# Group_02.net
KiCad netlist of a schematic drawn in EAGLE
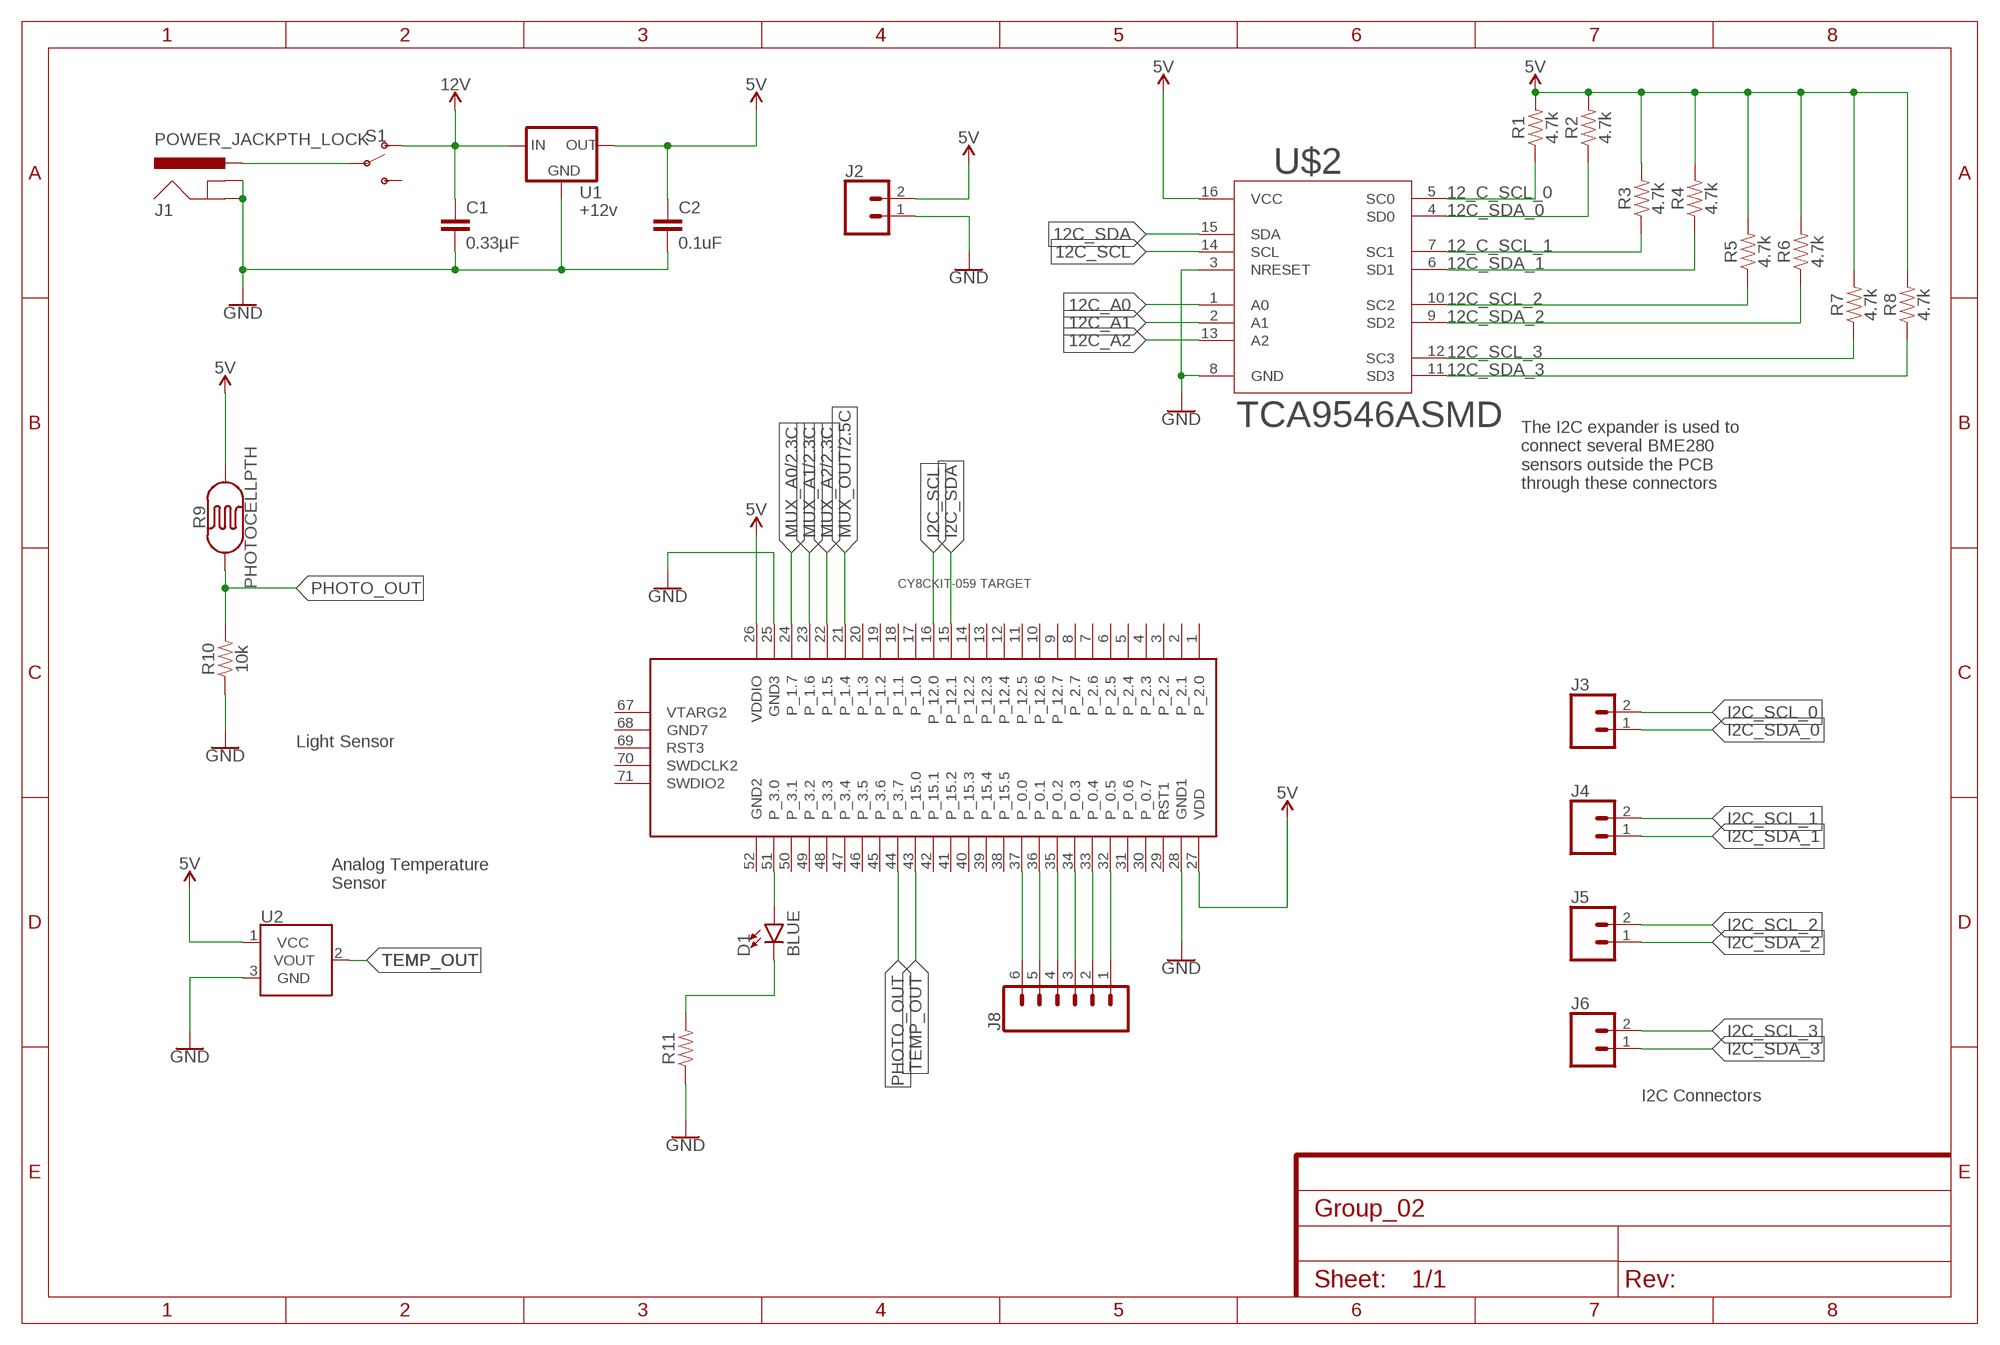
[diagram p0: schematic, sheet 1, part 1 of 2]
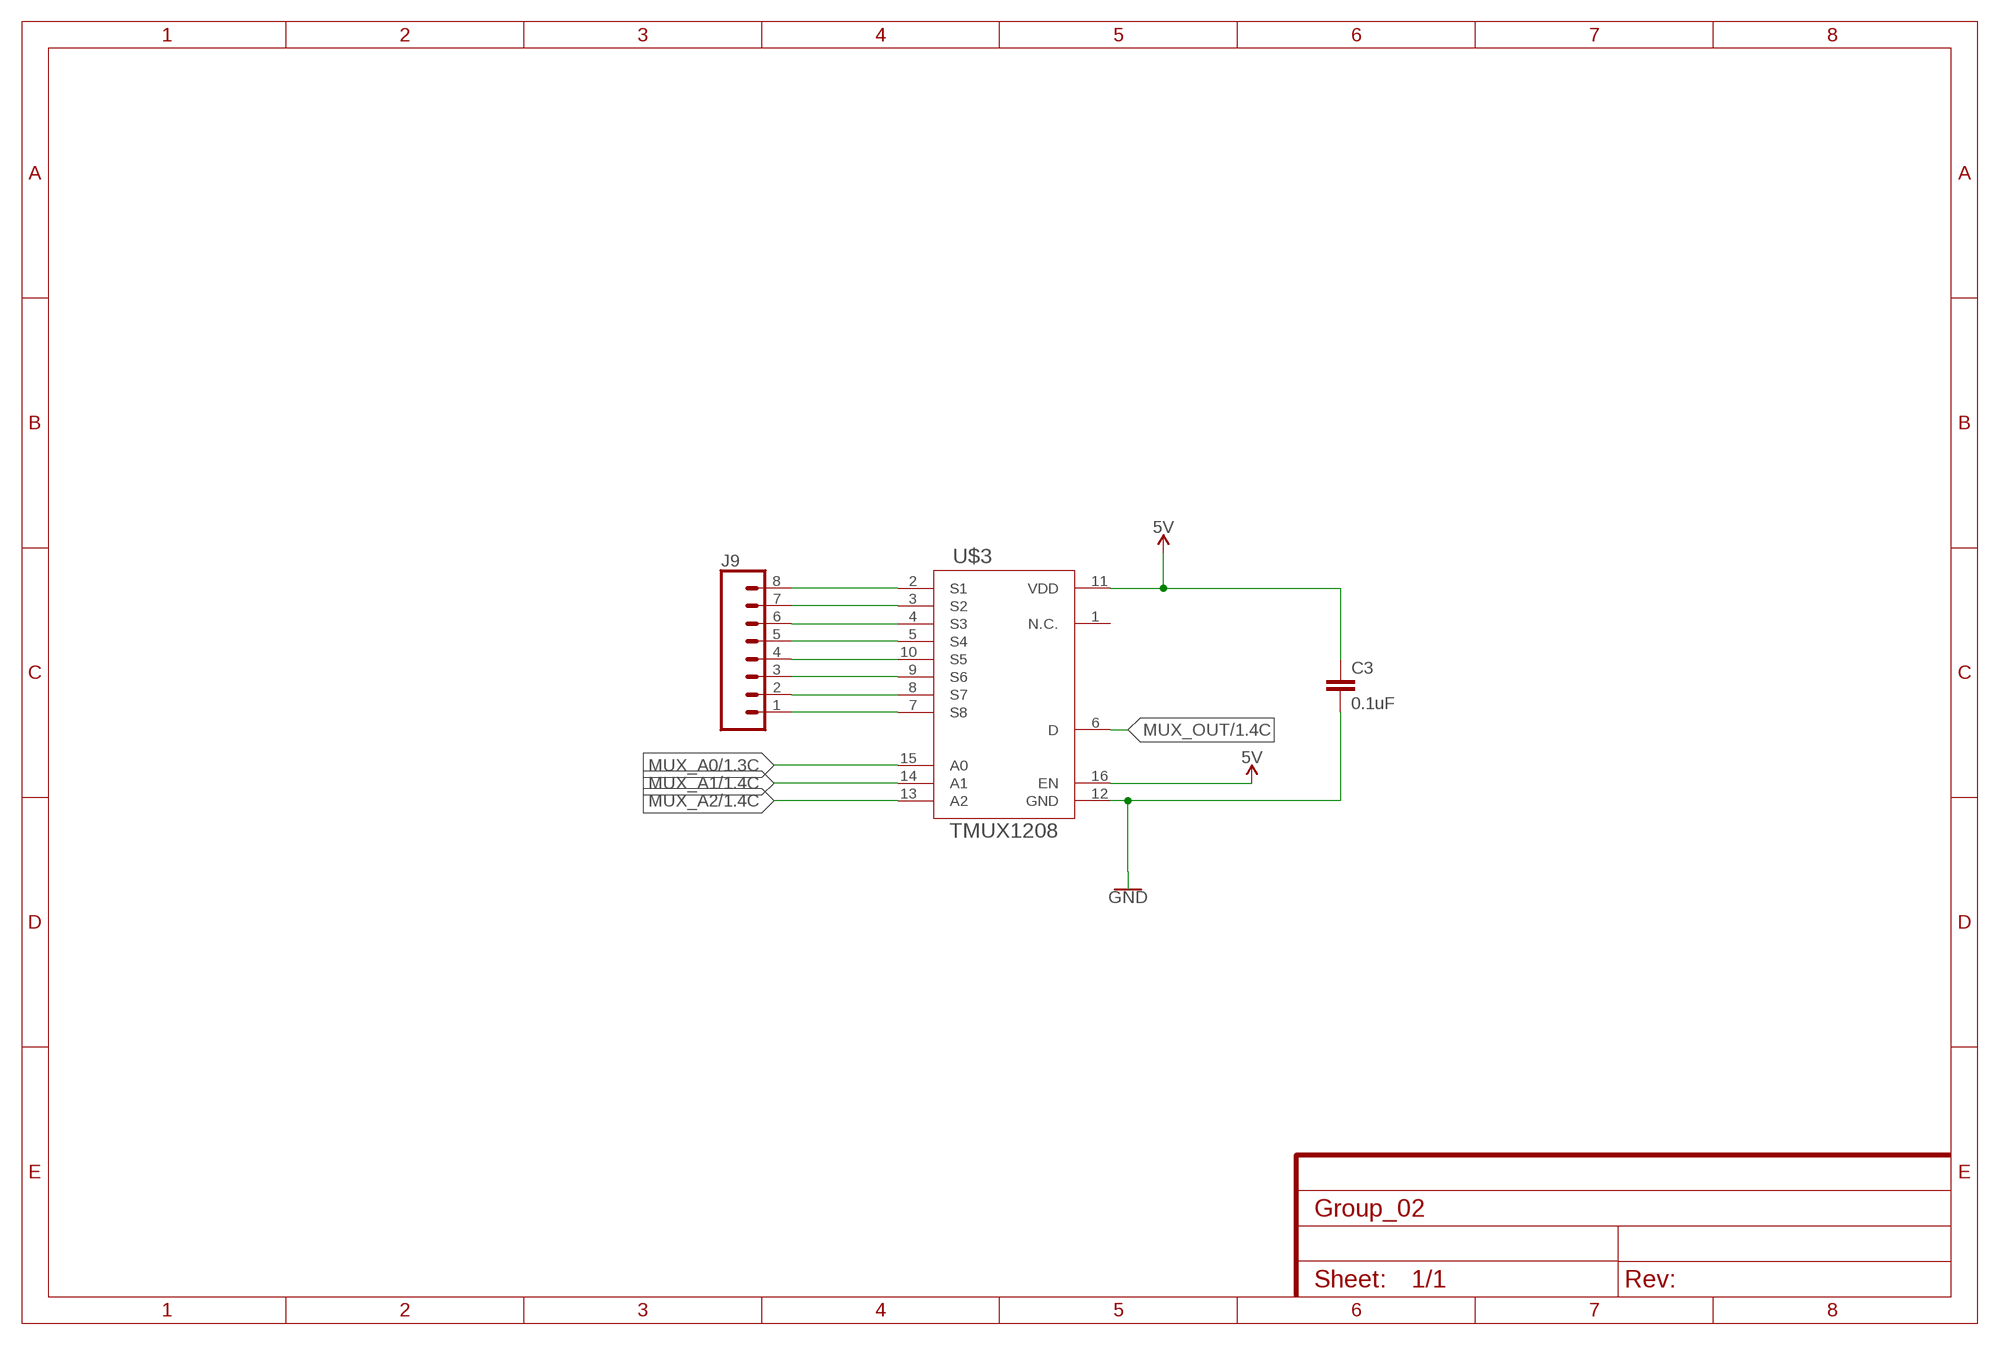
[diagram p1: schematic, sheet 1, part 2 of 2]

(export (version "E")
  (design (tool "Eeschema 10.0.6"))
  (components
    (comp (ref "C1")
      (value "0.33µF")
      (footprint "eagle-import:0805")
      (libsource (lib "eagle-import") (part "0.33UF/330NF-0805-50V-10%"))
    )
    (comp (ref "C2")
      (value "0.1uF")
      (footprint "eagle-import:CAP-PTH-SMALL-KIT")
      (libsource (lib "eagle-import") (part "0.1UF-KIT-EZ-50V-20%"))
    )
    (comp (ref "C3")
      (value "0.1uF")
      (footprint "eagle-import:CAP-PTH-SMALL-KIT")
      (libsource (lib "eagle-import") (part "0.1UF-KIT-EZ-50V-20%"))
    )
    (comp (ref "D1")
      (value "BLUE")
      (footprint "eagle-import:LED-1206")
      (libsource (lib "eagle-import") (part "LED-BLUE1206"))
    )
    (comp (ref "J1")
      (value "POWER_JACKPTH_LOCK")
      (footprint "eagle-import:POWER_JACK_PTH_LOCK")
      (libsource (lib "eagle-import") (part "POWER_JACKPTH_LOCK"))
    )
    (comp (ref "J2")
      (value "CONN_02")
      (footprint "eagle-import:1X02")
      (libsource (lib "eagle-import") (part "CONN_02"))
    )
    (comp (ref "J3")
      (value "CONN_02")
      (footprint "eagle-import:1X02")
      (libsource (lib "eagle-import") (part "CONN_02"))
    )
    (comp (ref "J4")
      (value "CONN_02")
      (footprint "eagle-import:1X02")
      (libsource (lib "eagle-import") (part "CONN_02"))
    )
    (comp (ref "J5")
      (value "CONN_02")
      (footprint "eagle-import:1X02")
      (libsource (lib "eagle-import") (part "CONN_02"))
    )
    (comp (ref "J6")
      (value "CONN_02")
      (footprint "eagle-import:1X02")
      (libsource (lib "eagle-import") (part "CONN_02"))
    )
    (comp (ref "J8")
      (value "CONN_06LOCK")
      (footprint "eagle-import:1X06_LOCK")
      (libsource (lib "eagle-import") (part "CONN_06LOCK"))
    )
    (comp (ref "J9")
      (value "CONN_08LOCK")
      (footprint "eagle-import:1X08_LOCK")
      (libsource (lib "eagle-import") (part "CONN_08LOCK"))
    )
    (comp (ref "R1")
      (value "4.7k")
      (footprint "eagle-import:0603")
      (libsource (lib "eagle-import") (part "4.7KOHM-0603-1/10W-1%"))
    )
    (comp (ref "R2")
      (value "4.7k")
      (footprint "eagle-import:0603")
      (libsource (lib "eagle-import") (part "4.7KOHM-0603-1/10W-1%"))
    )
    (comp (ref "R3")
      (value "4.7k")
      (footprint "eagle-import:0603")
      (libsource (lib "eagle-import") (part "4.7KOHM-0603-1/10W-1%"))
    )
    (comp (ref "R4")
      (value "4.7k")
      (footprint "eagle-import:0603")
      (libsource (lib "eagle-import") (part "4.7KOHM-0603-1/10W-1%"))
    )
    (comp (ref "R5")
      (value "4.7k")
      (footprint "eagle-import:0603")
      (libsource (lib "eagle-import") (part "4.7KOHM-0603-1/10W-1%"))
    )
    (comp (ref "R6")
      (value "4.7k")
      (footprint "eagle-import:0603")
      (libsource (lib "eagle-import") (part "4.7KOHM-0603-1/10W-1%"))
    )
    (comp (ref "R7")
      (value "4.7k")
      (footprint "eagle-import:0603")
      (libsource (lib "eagle-import") (part "4.7KOHM-0603-1/10W-1%"))
    )
    (comp (ref "R8")
      (value "4.7k")
      (footprint "eagle-import:0603")
      (libsource (lib "eagle-import") (part "4.7KOHM-0603-1/10W-1%"))
    )
    (comp (ref "R9")
      (value "PHOTOCELLPTH")
      (footprint "eagle-import:PHOTOCELL")
      (libsource (lib "eagle-import") (part "PHOTOCELLPTH"))
    )
    (comp (ref "R10")
      (value "10k")
      (footprint "eagle-import:0603")
      (libsource (lib "eagle-import") (part "10KOHM-0603-1/10W-1%"))
    )
    (comp (ref "R11")
      (value "RESISTORAXIAL-0.3")
      (footprint "eagle-import:AXIAL-0.3")
      (libsource (lib "eagle-import") (part "RESISTORAXIAL-0.3"))
    )
    (comp (ref "S1")
      (value "SWITCH-SPDT-PTH-11.6X4.0MM")
      (footprint "eagle-import:SWITCH_SPDT_PTH_11.6X4.0MM")
      (libsource (lib "eagle-import") (part "SWITCH-SPDT-PTH-11.6X4.0MM"))
    )
    (comp (ref "U$1")
      (value "CY8CKIT-059_TARGET")
      (footprint "eagle-import:CY8CKIT-059_TARGET")
      (libsource (lib "eagle-import") (part "CY8CKIT-059_TARGET"))
    )
    (comp (ref "U$2")
      (value "TCA9546ASMD")
      (footprint "eagle-import:TSSOP-16")
      (libsource (lib "eagle-import") (part "TCA9546ASMD"))
    )
    (comp (ref "U$3")
      (value "TMUX1208")
      (footprint "eagle-import:QFN-16")
      (libsource (lib "eagle-import") (part "TMUX1208"))
    )
    (comp (ref "U1")
      (value "+12v")
      (footprint "eagle-import:TO-252")
      (libsource (lib "eagle-import") (part "V_REG_78XX7812"))
    )
    (comp (ref "U2")
      (value "TMP36GT9")
      (footprint "eagle-import:TO-92")
      (libsource (lib "eagle-import") (part "TMP36GT9"))
    )
  )
  (nets
    (net (code "1") (name "/12C_SCL_2") (class "Default")
      (node (ref "R5") (pin "1") (pinfunction "1_1") (pintype "passive"))
      (node (ref "U$2") (pin "10") (pinfunction "SC2_10") (pintype "bidirectional"))
    )
    (net (code "2") (name "/12C_SCL_3") (class "Default")
      (node (ref "R7") (pin "1") (pinfunction "1_1") (pintype "passive"))
      (node (ref "U$2") (pin "12") (pinfunction "SC3_12") (pintype "bidirectional"))
    )
    (net (code "3") (name "/12C_SDA_0") (class "Default")
      (node (ref "R2") (pin "1") (pinfunction "1_1") (pintype "passive"))
      (node (ref "U$2") (pin "4") (pinfunction "SD0_4") (pintype "bidirectional"))
    )
    (net (code "4") (name "/12C_SDA_1") (class "Default")
      (node (ref "R4") (pin "1") (pinfunction "1_1") (pintype "passive"))
      (node (ref "U$2") (pin "6") (pinfunction "SD1_6") (pintype "bidirectional"))
    )
    (net (code "5") (name "/12C_SDA_2") (class "Default")
      (node (ref "R6") (pin "1") (pinfunction "1_1") (pintype "passive"))
      (node (ref "U$2") (pin "9") (pinfunction "SD2_9") (pintype "bidirectional"))
    )
    (net (code "6") (name "/12C_SDA_3") (class "Default")
      (node (ref "R8") (pin "1") (pinfunction "1_1") (pintype "passive"))
      (node (ref "U$2") (pin "11") (pinfunction "SD3_11") (pintype "bidirectional"))
    )
    (net (code "7") (name "/12_C_SCL_0") (class "Default")
      (node (ref "R1") (pin "1") (pinfunction "1_1") (pintype "passive"))
      (node (ref "U$2") (pin "5") (pinfunction "SC0_5") (pintype "bidirectional"))
    )
    (net (code "8") (name "/12_C_SCL_1") (class "Default")
      (node (ref "R3") (pin "1") (pinfunction "1_1") (pintype "passive"))
      (node (ref "U$2") (pin "7") (pinfunction "SC1_7") (pintype "bidirectional"))
    )
    (net (code "9") (name "5V") (class "Default")
      (node (ref "C2") (pin "1") (pinfunction "1_1") (pintype "passive"))
      (node (ref "C3") (pin "1") (pinfunction "1_1") (pintype "passive"))
      (node (ref "J2") (pin "2") (pinfunction "2_2") (pintype "passive"))
      (node (ref "R1") (pin "2") (pinfunction "2_2") (pintype "passive"))
      (node (ref "R2") (pin "2") (pinfunction "2_2") (pintype "passive"))
      (node (ref "R3") (pin "2") (pinfunction "2_2") (pintype "passive"))
      (node (ref "R4") (pin "2") (pinfunction "2_2") (pintype "passive"))
      (node (ref "R5") (pin "2") (pinfunction "2_2") (pintype "passive"))
      (node (ref "R6") (pin "2") (pinfunction "2_2") (pintype "passive"))
      (node (ref "R7") (pin "2") (pinfunction "2_2") (pintype "passive"))
      (node (ref "R8") (pin "2") (pinfunction "2_2") (pintype "passive"))
      (node (ref "R9") (pin "2") (pinfunction "P$2_2") (pintype "bidirectional"))
      (node (ref "U$1") (pin "26") (pinfunction "VDDIO_26") (pintype "bidirectional"))
      (node (ref "U$1") (pin "27") (pinfunction "VDD_27") (pintype "bidirectional"))
      (node (ref "U$2") (pin "16") (pinfunction "VCC_16") (pintype "bidirectional"))
      (node (ref "U$3") (pin "11") (pinfunction "VDD_11") (pintype "bidirectional"))
      (node (ref "U$3") (pin "16") (pinfunction "EN_16") (pintype "bidirectional"))
      (node (ref "U1") (pin "2") (pinfunction "OUT_2") (pintype "passive"))
      (node (ref "U2") (pin "1") (pinfunction "VCC_1") (pintype "bidirectional"))
    )
    (net (code "10") (name "12C_A0") (class "Default")
      (node (ref "U$2") (pin "1") (pinfunction "A0_1") (pintype "bidirectional"))
    )
    (net (code "11") (name "12C_A1") (class "Default")
      (node (ref "U$2") (pin "2") (pinfunction "A1_2") (pintype "bidirectional"))
    )
    (net (code "12") (name "12C_A2") (class "Default")
      (node (ref "U$2") (pin "13") (pinfunction "A2_13") (pintype "bidirectional"))
    )
    (net (code "13") (name "12C_SCL") (class "Default")
      (node (ref "U$2") (pin "14") (pinfunction "SCL_14") (pintype "bidirectional"))
    )
    (net (code "14") (name "12C_SDA") (class "Default")
      (node (ref "U$2") (pin "15") (pinfunction "SDA_15") (pintype "bidirectional"))
    )
    (net (code "15") (name "12V") (class "Default")
      (node (ref "C1") (pin "1") (pinfunction "1_1") (pintype "passive"))
      (node (ref "S1") (pin "1") (pinfunction "O_1") (pintype "passive"))
      (node (ref "U1") (pin "1") (pinfunction "IN_1") (pintype "input"))
    )
    (net (code "16") (name "GND") (class "Default")
      (node (ref "C1") (pin "2") (pinfunction "2_2") (pintype "passive"))
      (node (ref "C2") (pin "2") (pinfunction "2_2") (pintype "passive"))
      (node (ref "C3") (pin "2") (pinfunction "2_2") (pintype "passive"))
      (node (ref "J1") (pin "GND") (pinfunction "GND_GND") (pintype "bidirectional"))
      (node (ref "J1") (pin "GNDBREAK") (pinfunction "GNDBREAK_GNDBREAK") (pintype "bidirectional"))
      (node (ref "J2") (pin "1") (pinfunction "1_1") (pintype "passive"))
      (node (ref "R10") (pin "1") (pinfunction "1_1") (pintype "passive"))
      (node (ref "R11") (pin "P$1") (pinfunction "1_P$1") (pintype "passive"))
      (node (ref "U$1") (pin "25") (pinfunction "GND3_25") (pintype "bidirectional"))
      (node (ref "U$1") (pin "28") (pinfunction "GND1_28") (pintype "bidirectional"))
      (node (ref "U$2") (pin "3") (pinfunction "NRESET_3") (pintype "bidirectional"))
      (node (ref "U$2") (pin "8") (pinfunction "GND_8") (pintype "bidirectional"))
      (node (ref "U$3") (pin "12") (pinfunction "GND_12") (pintype "bidirectional"))
      (node (ref "U1") (pin "3") (pinfunction "GND_3") (pintype "input"))
      (node (ref "U2") (pin "3") (pinfunction "GND_3") (pintype "bidirectional"))
    )
    (net (code "17") (name "I2C_SCL") (class "Default")
      (node (ref "U$1") (pin "16") (pinfunction "P_12.0_16") (pintype "bidirectional"))
    )
    (net (code "18") (name "I2C_SCL_0") (class "Default")
      (node (ref "J3") (pin "2") (pinfunction "2_2") (pintype "passive"))
    )
    (net (code "19") (name "I2C_SCL_1") (class "Default")
      (node (ref "J4") (pin "2") (pinfunction "2_2") (pintype "passive"))
    )
    (net (code "20") (name "I2C_SCL_2") (class "Default")
      (node (ref "J5") (pin "2") (pinfunction "2_2") (pintype "passive"))
    )
    (net (code "21") (name "I2C_SCL_3") (class "Default")
      (node (ref "J6") (pin "2") (pinfunction "2_2") (pintype "passive"))
    )
    (net (code "22") (name "I2C_SDA") (class "Default")
      (node (ref "U$1") (pin "15") (pinfunction "P_12.1_15") (pintype "bidirectional"))
    )
    (net (code "23") (name "I2C_SDA_0") (class "Default")
      (node (ref "J3") (pin "1") (pinfunction "1_1") (pintype "passive"))
    )
    (net (code "24") (name "I2C_SDA_1") (class "Default")
      (node (ref "J4") (pin "1") (pinfunction "1_1") (pintype "passive"))
    )
    (net (code "25") (name "I2C_SDA_2") (class "Default")
      (node (ref "J5") (pin "1") (pinfunction "1_1") (pintype "passive"))
    )
    (net (code "26") (name "I2C_SDA_3") (class "Default")
      (node (ref "J6") (pin "1") (pinfunction "1_1") (pintype "passive"))
    )
    (net (code "27") (name "MUX_A0{slash}1.3C") (class "Default")
      (node (ref "U$3") (pin "15") (pinfunction "A0_15") (pintype "bidirectional"))
    )
    (net (code "28") (name "MUX_A0{slash}2.3C") (class "Default")
      (node (ref "U$1") (pin "24") (pinfunction "P_1.7_24") (pintype "bidirectional"))
    )
    (net (code "29") (name "MUX_A1{slash}1.4C") (class "Default")
      (node (ref "U$3") (pin "14") (pinfunction "A1_14") (pintype "bidirectional"))
    )
    (net (code "30") (name "MUX_A1{slash}2.3C") (class "Default")
      (node (ref "U$1") (pin "23") (pinfunction "P_1.6_23") (pintype "bidirectional"))
    )
    (net (code "31") (name "MUX_A2{slash}1.4C") (class "Default")
      (node (ref "U$3") (pin "13") (pinfunction "A2_13") (pintype "bidirectional"))
    )
    (net (code "32") (name "MUX_A2{slash}2.3C") (class "Default")
      (node (ref "U$1") (pin "22") (pinfunction "P_1.5_22") (pintype "bidirectional"))
    )
    (net (code "33") (name "MUX_OUT{slash}1.4C") (class "Default")
      (node (ref "U$3") (pin "6") (pinfunction "D_6") (pintype "bidirectional"))
    )
    (net (code "34") (name "MUX_OUT{slash}2.5C") (class "Default")
      (node (ref "U$1") (pin "21") (pinfunction "P_1.4_21") (pintype "bidirectional"))
    )
    (net (code "35") (name "Net-(R11-2)") (class "Default")
      (node (ref "D1") (pin "C") (pinfunction "C_C") (pintype "passive"))
      (node (ref "R11") (pin "P$2") (pinfunction "2_P$2") (pintype "passive"))
    )
    (net (code "36") (name "Net-(S1-P)") (class "Default")
      (node (ref "J1") (pin "PWR") (pinfunction "PWR_PWR") (pintype "bidirectional"))
      (node (ref "S1") (pin "2") (pinfunction "P_2") (pintype "passive"))
    )
    (net (code "37") (name "Net-(U$1-P_0.0)") (class "Default")
      (node (ref "J8") (pin "6") (pinfunction "6_6") (pintype "passive"))
      (node (ref "U$1") (pin "37") (pinfunction "P_0.0_37") (pintype "bidirectional"))
    )
    (net (code "38") (name "Net-(U$1-P_0.1)") (class "Default")
      (node (ref "J8") (pin "5") (pinfunction "5_5") (pintype "passive"))
      (node (ref "U$1") (pin "36") (pinfunction "P_0.1_36") (pintype "bidirectional"))
    )
    (net (code "39") (name "Net-(U$1-P_0.2)") (class "Default")
      (node (ref "J8") (pin "4") (pinfunction "4_4") (pintype "passive"))
      (node (ref "U$1") (pin "35") (pinfunction "P_0.2_35") (pintype "bidirectional"))
    )
    (net (code "40") (name "Net-(U$1-P_0.3)") (class "Default")
      (node (ref "J8") (pin "3") (pinfunction "3_3") (pintype "passive"))
      (node (ref "U$1") (pin "34") (pinfunction "P_0.3_34") (pintype "bidirectional"))
    )
    (net (code "41") (name "Net-(U$1-P_0.4)") (class "Default")
      (node (ref "J8") (pin "2") (pinfunction "2_2") (pintype "passive"))
      (node (ref "U$1") (pin "33") (pinfunction "P_0.4_33") (pintype "bidirectional"))
    )
    (net (code "42") (name "Net-(U$1-P_0.5)") (class "Default")
      (node (ref "J8") (pin "1") (pinfunction "1_1") (pintype "passive"))
      (node (ref "U$1") (pin "32") (pinfunction "P_0.5_32") (pintype "bidirectional"))
    )
    (net (code "43") (name "Net-(U$1-P_3.0)") (class "Default")
      (node (ref "D1") (pin "A") (pinfunction "A_A") (pintype "passive"))
      (node (ref "U$1") (pin "51") (pinfunction "P_3.0_51") (pintype "bidirectional"))
    )
    (net (code "44") (name "Net-(U$3-S1)") (class "Default")
      (node (ref "J9") (pin "8") (pinfunction "8_8") (pintype "passive"))
      (node (ref "U$3") (pin "2") (pinfunction "S1_2") (pintype "bidirectional"))
    )
    (net (code "45") (name "Net-(U$3-S2)") (class "Default")
      (node (ref "J9") (pin "7") (pinfunction "7_7") (pintype "passive"))
      (node (ref "U$3") (pin "3") (pinfunction "S2_3") (pintype "bidirectional"))
    )
    (net (code "46") (name "Net-(U$3-S3)") (class "Default")
      (node (ref "J9") (pin "6") (pinfunction "6_6") (pintype "passive"))
      (node (ref "U$3") (pin "4") (pinfunction "S3_4") (pintype "bidirectional"))
    )
    (net (code "47") (name "Net-(U$3-S4)") (class "Default")
      (node (ref "J9") (pin "5") (pinfunction "5_5") (pintype "passive"))
      (node (ref "U$3") (pin "5") (pinfunction "S4_5") (pintype "bidirectional"))
    )
    (net (code "48") (name "Net-(U$3-S5)") (class "Default")
      (node (ref "J9") (pin "4") (pinfunction "4_4") (pintype "passive"))
      (node (ref "U$3") (pin "10") (pinfunction "S5_10") (pintype "bidirectional"))
    )
    (net (code "49") (name "Net-(U$3-S6)") (class "Default")
      (node (ref "J9") (pin "3") (pinfunction "3_3") (pintype "passive"))
      (node (ref "U$3") (pin "9") (pinfunction "S6_9") (pintype "bidirectional"))
    )
    (net (code "50") (name "Net-(U$3-S7)") (class "Default")
      (node (ref "J9") (pin "2") (pinfunction "2_2") (pintype "passive"))
      (node (ref "U$3") (pin "8") (pinfunction "S7_8") (pintype "bidirectional"))
    )
    (net (code "51") (name "Net-(U$3-S8)") (class "Default")
      (node (ref "J9") (pin "1") (pinfunction "1_1") (pintype "passive"))
      (node (ref "U$3") (pin "7") (pinfunction "S8_7") (pintype "bidirectional"))
    )
    (net (code "52") (name "PHOTO_OUT") (class "Default")
      (node (ref "R10") (pin "2") (pinfunction "2_2") (pintype "passive"))
      (node (ref "R9") (pin "1") (pinfunction "P$1_1") (pintype "bidirectional"))
      (node (ref "U$1") (pin "44") (pinfunction "P_3.7_44") (pintype "bidirectional"))
    )
    (net (code "53") (name "TEMP_OUT") (class "Default")
      (node (ref "U$1") (pin "43") (pinfunction "P_15.0_43") (pintype "bidirectional"))
      (node (ref "U2") (pin "2") (pinfunction "VOUT_2") (pintype "bidirectional"))
    )
    (net (code "54") (name "unconnected-(S1-S-Pad3)") (class "Default")
      (node (ref "S1") (pin "3") (pinfunction "S_3") (pintype "passive"))
    )
    (net (code "55") (name "unconnected-(U$1-GND2-Pad52)") (class "Default")
      (node (ref "U$1") (pin "52") (pinfunction "GND2_52") (pintype "bidirectional"))
    )
    (net (code "56") (name "unconnected-(U$1-GND7-Pad68)") (class "Default")
      (node (ref "U$1") (pin "68") (pinfunction "GND7_68") (pintype "bidirectional"))
    )
    (net (code "57") (name "unconnected-(U$1-P_0.6-Pad31)") (class "Default")
      (node (ref "U$1") (pin "31") (pinfunction "P_0.6_31") (pintype "bidirectional"))
    )
    (net (code "58") (name "unconnected-(U$1-P_0.7-Pad30)") (class "Default")
      (node (ref "U$1") (pin "30") (pinfunction "P_0.7_30") (pintype "bidirectional"))
    )
    (net (code "59") (name "unconnected-(U$1-P_1.0-Pad17)") (class "Default")
      (node (ref "U$1") (pin "17") (pinfunction "P_1.0_17") (pintype "bidirectional"))
    )
    (net (code "60") (name "unconnected-(U$1-P_1.1-Pad18)") (class "Default")
      (node (ref "U$1") (pin "18") (pinfunction "P_1.1_18") (pintype "bidirectional"))
    )
    (net (code "61") (name "unconnected-(U$1-P_1.2-Pad19)") (class "Default")
      (node (ref "U$1") (pin "19") (pinfunction "P_1.2_19") (pintype "bidirectional"))
    )
    (net (code "62") (name "unconnected-(U$1-P_1.3-Pad20)") (class "Default")
      (node (ref "U$1") (pin "20") (pinfunction "P_1.3_20") (pintype "bidirectional"))
    )
    (net (code "63") (name "unconnected-(U$1-P_2.0-Pad1)") (class "Default")
      (node (ref "U$1") (pin "1") (pinfunction "P_2.0_1") (pintype "bidirectional"))
    )
    (net (code "64") (name "unconnected-(U$1-P_2.1-Pad2)") (class "Default")
      (node (ref "U$1") (pin "2") (pinfunction "P_2.1_2") (pintype "bidirectional"))
    )
    (net (code "65") (name "unconnected-(U$1-P_2.2-Pad3)") (class "Default")
      (node (ref "U$1") (pin "3") (pinfunction "P_2.2_3") (pintype "bidirectional"))
    )
    (net (code "66") (name "unconnected-(U$1-P_2.3-Pad4)") (class "Default")
      (node (ref "U$1") (pin "4") (pinfunction "P_2.3_4") (pintype "bidirectional"))
    )
    (net (code "67") (name "unconnected-(U$1-P_2.4-Pad5)") (class "Default")
      (node (ref "U$1") (pin "5") (pinfunction "P_2.4_5") (pintype "bidirectional"))
    )
    (net (code "68") (name "unconnected-(U$1-P_2.5-Pad6)") (class "Default")
      (node (ref "U$1") (pin "6") (pinfunction "P_2.5_6") (pintype "bidirectional"))
    )
    (net (code "69") (name "unconnected-(U$1-P_2.6-Pad7)") (class "Default")
      (node (ref "U$1") (pin "7") (pinfunction "P_2.6_7") (pintype "bidirectional"))
    )
    (net (code "70") (name "unconnected-(U$1-P_2.7-Pad8)") (class "Default")
      (node (ref "U$1") (pin "8") (pinfunction "P_2.7_8") (pintype "bidirectional"))
    )
    (net (code "71") (name "unconnected-(U$1-P_3.1-Pad50)") (class "Default")
      (node (ref "U$1") (pin "50") (pinfunction "P_3.1_50") (pintype "bidirectional"))
    )
    (net (code "72") (name "unconnected-(U$1-P_3.2-Pad49)") (class "Default")
      (node (ref "U$1") (pin "49") (pinfunction "P_3.2_49") (pintype "bidirectional"))
    )
    (net (code "73") (name "unconnected-(U$1-P_3.3-Pad48)") (class "Default")
      (node (ref "U$1") (pin "48") (pinfunction "P_3.3_48") (pintype "bidirectional"))
    )
    (net (code "74") (name "unconnected-(U$1-P_3.4-Pad47)") (class "Default")
      (node (ref "U$1") (pin "47") (pinfunction "P_3.4_47") (pintype "bidirectional"))
    )
    (net (code "75") (name "unconnected-(U$1-P_3.5-Pad46)") (class "Default")
      (node (ref "U$1") (pin "46") (pinfunction "P_3.5_46") (pintype "bidirectional"))
    )
    (net (code "76") (name "unconnected-(U$1-P_3.6-Pad45)") (class "Default")
      (node (ref "U$1") (pin "45") (pinfunction "P_3.6_45") (pintype "bidirectional"))
    )
    (net (code "77") (name "unconnected-(U$1-P_12.2-Pad14)") (class "Default")
      (node (ref "U$1") (pin "14") (pinfunction "P_12.2_14") (pintype "bidirectional"))
    )
    (net (code "78") (name "unconnected-(U$1-P_12.3-Pad13)") (class "Default")
      (node (ref "U$1") (pin "13") (pinfunction "P_12.3_13") (pintype "bidirectional"))
    )
    (net (code "79") (name "unconnected-(U$1-P_12.4-Pad12)") (class "Default")
      (node (ref "U$1") (pin "12") (pinfunction "P_12.4_12") (pintype "bidirectional"))
    )
    (net (code "80") (name "unconnected-(U$1-P_12.5-Pad11)") (class "Default")
      (node (ref "U$1") (pin "11") (pinfunction "P_12.5_11") (pintype "bidirectional"))
    )
    (net (code "81") (name "unconnected-(U$1-P_12.6-Pad10)") (class "Default")
      (node (ref "U$1") (pin "10") (pinfunction "P_12.6_10") (pintype "bidirectional"))
    )
    (net (code "82") (name "unconnected-(U$1-P_12.7-Pad9)") (class "Default")
      (node (ref "U$1") (pin "9") (pinfunction "P_12.7_9") (pintype "bidirectional"))
    )
    (net (code "83") (name "unconnected-(U$1-P_15.1-Pad42)") (class "Default")
      (node (ref "U$1") (pin "42") (pinfunction "P_15.1_42") (pintype "bidirectional"))
    )
    (net (code "84") (name "unconnected-(U$1-P_15.2-Pad41)") (class "Default")
      (node (ref "U$1") (pin "41") (pinfunction "P_15.2_41") (pintype "bidirectional"))
    )
    (net (code "85") (name "unconnected-(U$1-P_15.3-Pad40)") (class "Default")
      (node (ref "U$1") (pin "40") (pinfunction "P_15.3_40") (pintype "bidirectional"))
    )
    (net (code "86") (name "unconnected-(U$1-P_15.4-Pad39)") (class "Default")
      (node (ref "U$1") (pin "39") (pinfunction "P_15.4_39") (pintype "bidirectional"))
    )
    (net (code "87") (name "unconnected-(U$1-P_15.5-Pad38)") (class "Default")
      (node (ref "U$1") (pin "38") (pinfunction "P_15.5_38") (pintype "bidirectional"))
    )
    (net (code "88") (name "unconnected-(U$1-RST1-Pad29)") (class "Default")
      (node (ref "U$1") (pin "29") (pinfunction "RST1_29") (pintype "bidirectional"))
    )
    (net (code "89") (name "unconnected-(U$1-RST3-Pad69)") (class "Default")
      (node (ref "U$1") (pin "69") (pinfunction "RST3_69") (pintype "bidirectional"))
    )
    (net (code "90") (name "unconnected-(U$1-SWDCLK2-Pad70)") (class "Default")
      (node (ref "U$1") (pin "70") (pinfunction "SWDCLK2_70") (pintype "bidirectional"))
    )
    (net (code "91") (name "unconnected-(U$1-SWDIO2-Pad71)") (class "Default")
      (node (ref "U$1") (pin "71") (pinfunction "SWDIO2_71") (pintype "bidirectional"))
    )
    (net (code "92") (name "unconnected-(U$1-VTARG2-Pad67)") (class "Default")
      (node (ref "U$1") (pin "67") (pinfunction "VTARG2_67") (pintype "bidirectional"))
    )
    (net (code "93") (name "unconnected-(U$3-N.C.-Pad1)") (class "Default")
      (node (ref "U$3") (pin "1") (pinfunction "N.C._1") (pintype "bidirectional"))
    )
  )
)
